# Rotary_breakout_module.net
KiCad netlist of a schematic drawn in Altium Designer
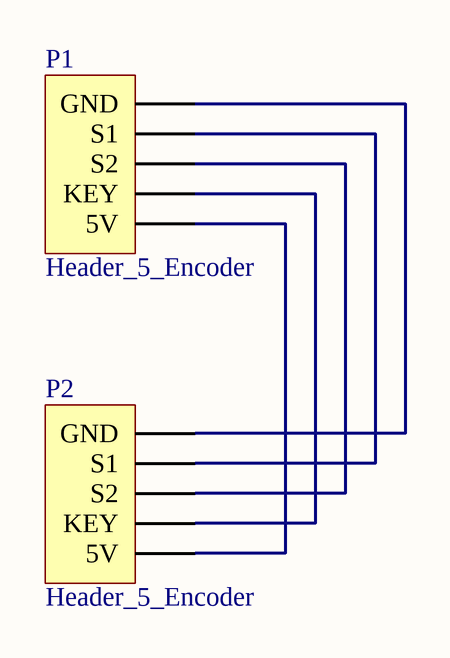
[diagram p0: Rotary_breakout_module.SchDoc]

(export (version "E")
  (design (tool "Eeschema 10.0.6"))
  (components
    (comp (ref "P1")
      (value "Header_5_Encoder")
      (footprint "HDR1X5_Encoder")
      (description "Header 5 pins to connect one encoder")
      (libsource (lib "Schlib1") (part "Header_5_Encoder"))
    )
    (comp (ref "P2")
      (value "Header_5_Encoder")
      (footprint "HDR1X5_Encoder")
      (description "Header 5 pins to connect one encoder")
      (libsource (lib "Schlib1") (part "Header_5_Encoder"))
    )
  )
  (nets
    (net (code "1") (name "Net-(P1-5V)") (class "Default")
      (node (ref "P1") (pin "5") (pinfunction "5V_5") (pintype "passive"))
      (node (ref "P2") (pin "5") (pinfunction "5V_5") (pintype "passive"))
    )
    (net (code "2") (name "Net-(P1-GND)") (class "Default")
      (node (ref "P1") (pin "1") (pinfunction "GND_1") (pintype "passive"))
      (node (ref "P2") (pin "1") (pinfunction "GND_1") (pintype "passive"))
    )
    (net (code "3") (name "Net-(P1-KEY)") (class "Default")
      (node (ref "P1") (pin "4") (pinfunction "KEY_4") (pintype "passive"))
      (node (ref "P2") (pin "4") (pinfunction "KEY_4") (pintype "passive"))
    )
    (net (code "4") (name "Net-(P1-S1)") (class "Default")
      (node (ref "P1") (pin "2") (pinfunction "S1_2") (pintype "passive"))
      (node (ref "P2") (pin "2") (pinfunction "S1_2") (pintype "passive"))
    )
    (net (code "5") (name "Net-(P1-S2)") (class "Default")
      (node (ref "P1") (pin "3") (pinfunction "S2_3") (pintype "passive"))
      (node (ref "P2") (pin "3") (pinfunction "S2_3") (pintype "passive"))
    )
  )
)
